# MIXR_Processing_-_QSPI_NOR_Flash.net
KiCad netlist of a schematic drawn in Altium Designer
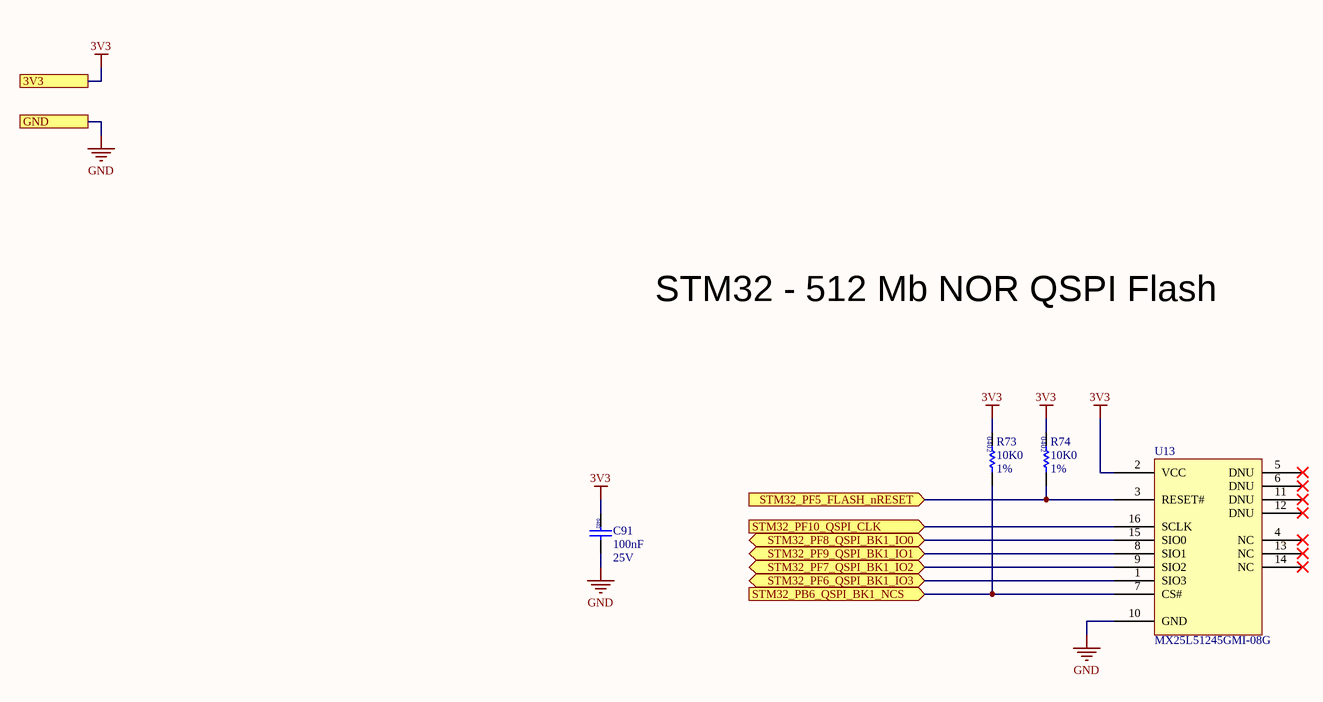
[diagram p0: MIXR Processing - QSPI NOR Flash.SchDoc]

(export (version "E")
  (design (tool "Eeschema 10.0.6"))
  (components
    (comp (ref "C91")
      (value "CAP CER 0.1UF 16V X7R 0402")
      (footprint "CAP 0402")
      (description "Cap Ceramic 0.1uF 25V X7R 10% SMD 0402 125C Paper T/R")
      (fields
        (field (name "TOLERANCE") "10%")
        (field (name "CAPACITANCE") "100nF")
        (field (name "VOLTAGE") "25V")
        (field (name "MANUFACTURER") "Murata")
      )
      (libsource (lib "Schematic Diagrams") (part "CAP CER 0.1UF 16V X7R 0402"))
    )
    (comp (ref "R73")
      (value "RES 10K OHM 1% 1/16W 0402")
      (footprint "RES 0402")
      (description "Surface Mount Thick Film Resistor, Rc Series, 10 Kohm, 62.5 Mw, - 1%, 50 V, 0402 [1005 Metric]")
      (fields
        (field (name "MANUFACTURER") "Yageo")
        (field (name "MANUFACTURER PART NUMBER") "RC0402FR-0710KL")
        (field (name "RESISTANCE") "10K0")
        (field (name "TOLERANCE") "1%")
      )
      (libsource (lib "Schematic Diagrams") (part "RES 10K OHM 1% 1/16W 0402"))
    )
    (comp (ref "R74")
      (value "RES 10K OHM 1% 1/16W 0402")
      (footprint "RES 0402")
      (description "Surface Mount Thick Film Resistor, Rc Series, 10 Kohm, 62.5 Mw, - 1%, 50 V, 0402 [1005 Metric]")
      (fields
        (field (name "MANUFACTURER") "Yageo")
        (field (name "MANUFACTURER PART NUMBER") "RC0402FR-0710KL")
        (field (name "RESISTANCE") "10K0")
        (field (name "TOLERANCE") "1%")
      )
      (libsource (lib "Schematic Diagrams") (part "RES 10K OHM 1% 1/16W 0402"))
    )
    (comp (ref "U13")
      (value "IC FLASH NOR 512Mb SPI 166MHz 16-SOP")
      (footprint "SOP127P1030X265-16N")
      (description "FLASH - NOR Memory IC 512Mb (64M x 8) SPI 166MHz 16-SOP")
      (fields
        (field (name "MANUFACTURER") "Macronix")
        (field (name "MANUFACTURER PART NUMBER") "MX25L51245GMI-08G")
      )
      (libsource (lib "Schematic Diagrams") (part "IC FLASH NOR 512Mb SPI 166MHz 16-SOP"))
    )
  )
  (nets
    (net (code "1") (name "/STM32_PB6_QSPI_BK1_NCS") (class "Default")
      (node (ref "R73") (pin "2") (pinfunction "2_2") (pintype "passive"))
      (node (ref "U13") (pin "7") (pinfunction "CS#_7") (pintype "passive"))
    )
    (net (code "2") (name "/STM32_PF5_FLASH_nRESET") (class "Default")
      (node (ref "R74") (pin "2") (pinfunction "2_2") (pintype "passive"))
      (node (ref "U13") (pin "3") (pinfunction "RESET#_3") (pintype "passive"))
    )
    (net (code "3") (name "/STM32_PF6_QSPI_BK1_IO3") (class "Default")
      (node (ref "U13") (pin "1") (pinfunction "SIO3_1") (pintype "passive"))
    )
    (net (code "4") (name "/STM32_PF7_QSPI_BK1_IO2") (class "Default")
      (node (ref "U13") (pin "9") (pinfunction "SIO2_9") (pintype "passive"))
    )
    (net (code "5") (name "/STM32_PF8_QSPI_BK1_IO0") (class "Default")
      (node (ref "U13") (pin "15") (pinfunction "SIO0_15") (pintype "passive"))
    )
    (net (code "6") (name "/STM32_PF9_QSPI_BK1_IO1") (class "Default")
      (node (ref "U13") (pin "8") (pinfunction "SIO1_8") (pintype "passive"))
    )
    (net (code "7") (name "/STM32_PF10_QSPI_CLK") (class "Default")
      (node (ref "U13") (pin "16") (pinfunction "SCLK_16") (pintype "passive"))
    )
    (net (code "8") (name "3V3") (class "Default")
      (node (ref "C91") (pin "1") (pinfunction "1_1") (pintype "passive"))
      (node (ref "R73") (pin "1") (pinfunction "1_1") (pintype "passive"))
      (node (ref "R74") (pin "1") (pinfunction "1_1") (pintype "passive"))
      (node (ref "U13") (pin "2") (pinfunction "VCC_2") (pintype "passive"))
    )
    (net (code "9") (name "GND") (class "Default")
      (node (ref "C91") (pin "2") (pinfunction "2_2") (pintype "passive"))
      (node (ref "U13") (pin "10") (pinfunction "GND_10") (pintype "passive"))
    )
    (net (code "10") (name "unconnected-(U13-DNU-Pad5)") (class "Default")
      (node (ref "U13") (pin "5") (pinfunction "DNU_5") (pintype "passive+no_connect"))
    )
    (net (code "11") (name "unconnected-(U13-DNU-Pad6)") (class "Default")
      (node (ref "U13") (pin "6") (pinfunction "DNU_6") (pintype "passive+no_connect"))
    )
    (net (code "12") (name "unconnected-(U13-DNU-Pad11)") (class "Default")
      (node (ref "U13") (pin "11") (pinfunction "DNU_11") (pintype "passive+no_connect"))
    )
    (net (code "13") (name "unconnected-(U13-DNU-Pad12)") (class "Default")
      (node (ref "U13") (pin "12") (pinfunction "DNU_12") (pintype "passive+no_connect"))
    )
    (net (code "14") (name "unconnected-(U13-NC-Pad4)") (class "Default")
      (node (ref "U13") (pin "4") (pinfunction "NC_4") (pintype "passive+no_connect"))
    )
    (net (code "15") (name "unconnected-(U13-NC-Pad13)") (class "Default")
      (node (ref "U13") (pin "13") (pinfunction "NC_13") (pintype "passive+no_connect"))
    )
    (net (code "16") (name "unconnected-(U13-NC-Pad14)") (class "Default")
      (node (ref "U13") (pin "14") (pinfunction "NC_14") (pintype "passive+no_connect"))
    )
  )
)
